# cSLIM-SA_connectors.net
KiCad netlist of a schematic drawn in Altium Designer
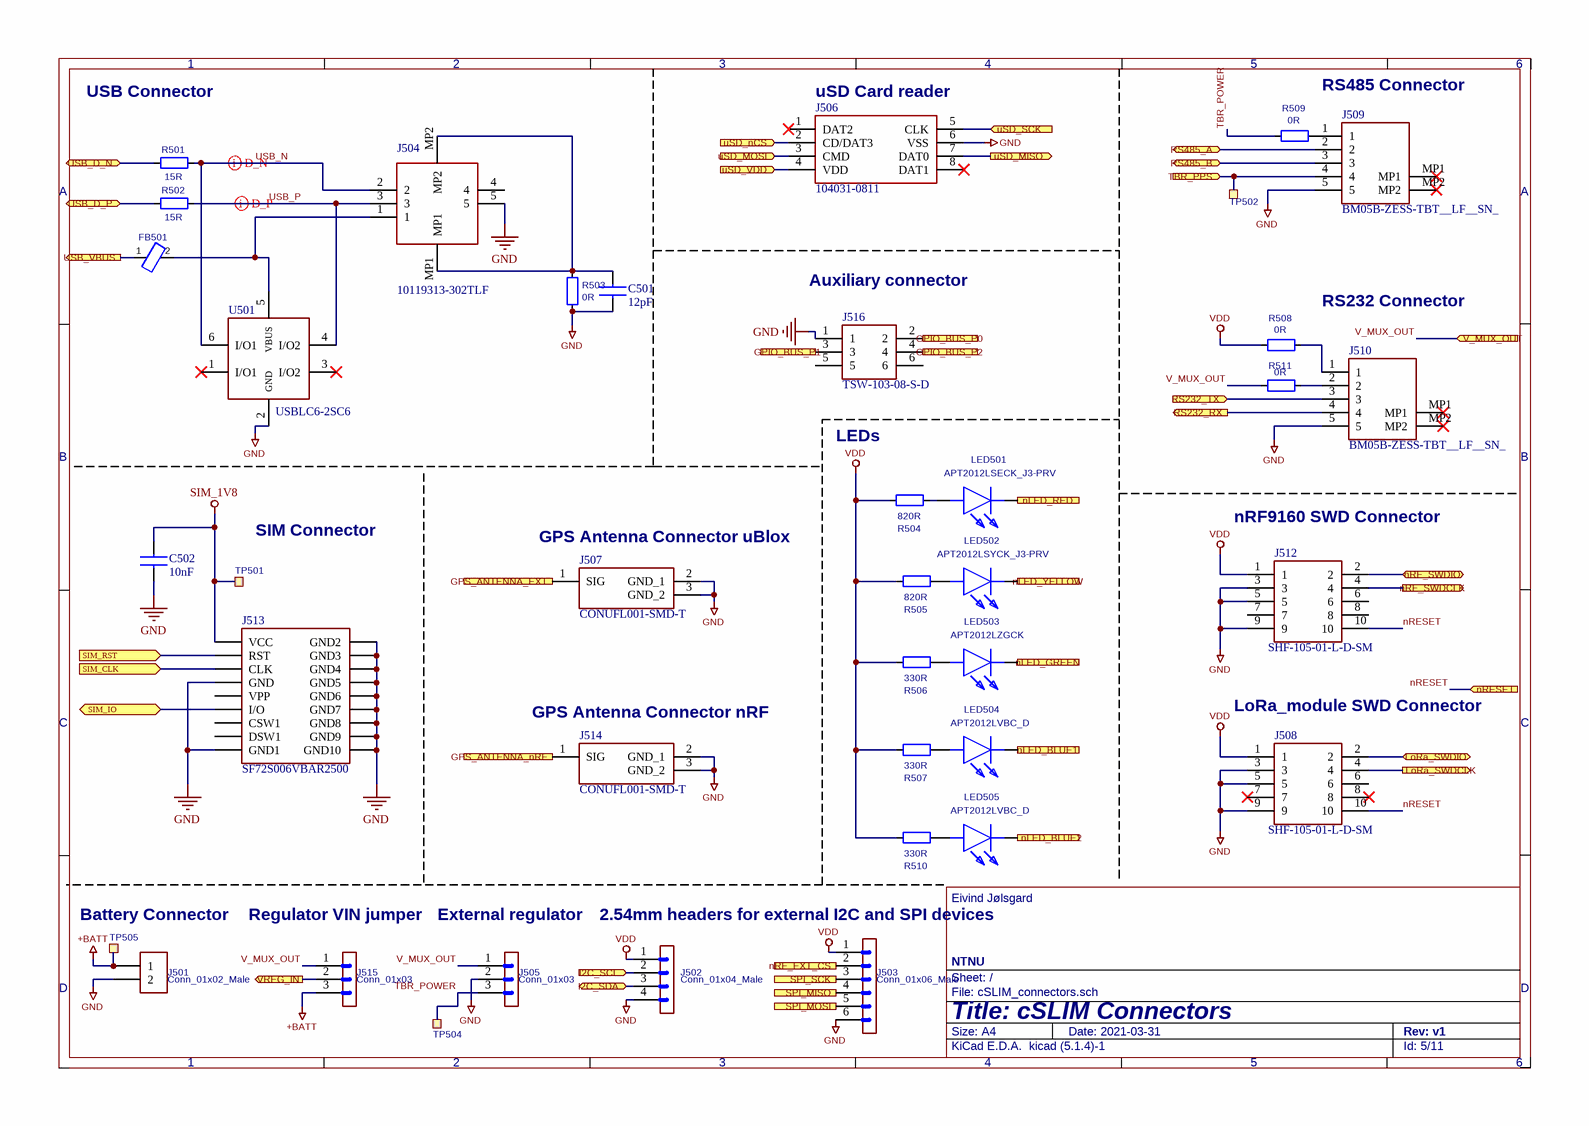
[diagram p0: cSLIM-SA_connectors.SchDoc]

(export (version "E")
  (design (tool "Eeschema 10.0.6"))
  (components
    (comp (ref "C501")
      (value "12pF")
      (footprint "cSLIM-SA:CAPC1608X90N")
      (description "Capacitor")
      (fields
        (field (name "MANUFACTURER_PART_NUMBER") "06033G104ZAT2A")
        (field (name "MOUSER PART NUMBER") "581-06033G104Z")
      )
      (libsource (lib "cSLIM-SA") (part "C"))
    )
    (comp (ref "C502")
      (value "10nF")
      (footprint "cSLIM-SA:CAPC1608X90N")
      (description "Capacitor")
      (fields
        (field (name "MANUFACTURER_PART_NUMBER") "06033G104ZAT2A")
        (field (name "MOUSER PART NUMBER") "581-06033G104Z")
      )
      (libsource (lib "cSLIM-SA") (part "C"))
    )
    (comp (ref "FB501")
      (value "500mA")
      (footprint "CAPC1608X90N")
      (libsource (lib "cSLIM-SA") (part "Ferrite_Bead"))
    )
    (comp (ref "J501")
      (value "Conn_01x02_Male")
      (footprint "cSLIM-SA:SHDR2W64P0X254_1X2_737X660X1181P")
      (description "Connector")
      (fields
        (field (name "MANUFACTURER_PART_NUMBER") "70543-0001")
        (field (name "MOUSER PART NUMBER") "538-70543-0001")
      )
      (libsource (lib "cSLIM-SA") (part "70543-0001"))
    )
    (comp (ref "J502")
      (value "Conn_01x04_Male")
      (footprint "cSLIM-SA:HDRV4W64P0X254_1X4_1016X250X901P")
      (description "Connector")
      (fields (field (name "MANUFACTURER_PART_NUMBER") "PH1-04-UA"))
      (libsource (lib "cSLIM-SA") (part "PH1-04-UA"))
    )
    (comp (ref "J503")
      (value "Conn_01x06_Male")
      (footprint "cSLIM-SA:HDRV6W64P0X254_1X6_1524X254X869P")
      (description "Connector")
      (fields
        (field (name "MANUFACTURER_PART_NUMBER") "61300611121")
        (field (name "MOUSER PART NUMBER") "710-61300611121")
      )
      (libsource (lib "cSLIM-SA") (part "61300611121"))
    )
    (comp (ref "J504")
      (value "10119313-302TLF")
      (footprint "cSLIM-SA:10119313302TLF")
      (description "Connector")
      (fields (field (name "MOUSER PART NUMBER") "649-10119313-302TLF"))
      (libsource (lib "cSLIM-SA") (part "10119313-302TLF"))
    )
    (comp (ref "J505")
      (value "Conn_01x03")
      (footprint "cSLIM-SA:HDRV3W64P0X254_1X3_762X254X869P")
      (description "Connector")
      (fields
        (field (name "MANUFACTURER_PART_NUMBER") "61300311121")
        (field (name "MOUSER PART NUMBER") "710-61300311121")
      )
      (libsource (lib "cSLIM-SA") (part "61300311121"))
    )
    (comp (ref "J506")
      (value "104031-0811")
      (footprint "cSLIM-SA:1040310811")
      (description "Connector")
      (fields (field (name "MOUSER PART NUMBER") "538-104031-0811"))
      (libsource (lib "cSLIM-SA") (part "104031-0811"))
    )
    (comp (ref "J507")
      (value "CONUFL001-SMD-T")
      (footprint "cSLIM-SA:CONUFL001-SMD")
      (description "Connector")
      (fields (field (name "MOUSER PART NUMBER") "712-CONUFL001-SMD-T"))
      (libsource (lib "cSLIM-SA") (part "CONUFL001-SMD-T"))
    )
    (comp (ref "J508")
      (value "SHF-105-01-L-D-SM")
      (footprint "cSLIM-SA:SHF10501LDSMLCKTR")
      (description "Connector")
      (fields (field (name "MANUFACTURER_PART_NUMBER") "SHF-105-01-L-D-SM-LC-K-TR"))
      (libsource (lib "cSLIM-SA") (part "SHF-105-01-L-D-SM-LC-K-TR"))
    )
    (comp (ref "J509")
      (value "BM05B-ZESS-TBT__LF__SN_")
      (footprint "cSLIM-SA:BM05BZESSTBTLFSN")
      (description "Connector")
      (fields (field (name "MANUFACTURER_PART_NUMBER") "BM05B-ZESS-TBT (LF)(SN)"))
      (libsource (lib "cSLIM-SA") (part "BM05B-ZESS-TBT__LF__SN_"))
    )
    (comp (ref "J510")
      (value "BM05B-ZESS-TBT__LF__SN_")
      (footprint "cSLIM-SA:BM05BZESSTBTLFSN")
      (description "Connector")
      (fields (field (name "MANUFACTURER_PART_NUMBER") "BM05B-ZESS-TBT (LF)(SN)"))
      (libsource (lib "cSLIM-SA") (part "BM05B-ZESS-TBT__LF__SN_"))
    )
    (comp (ref "J512")
      (value "SHF-105-01-L-D-SM")
      (footprint "cSLIM-SA:SHF10501LDSMLCKTR")
      (description "Connector")
      (fields (field (name "MANUFACTURER_PART_NUMBER") "SHF-105-01-L-D-SM-LC-K-TR"))
      (libsource (lib "cSLIM-SA") (part "SHF-105-01-L-D-SM-LC-K-TR"))
    )
    (comp (ref "J513")
      (value "SF72S006VBAR2500")
      (footprint "cSLIM-SA:SF72S006VBAR2500")
      (description "Connector")
      (fields (field (name "MOUSER PART NUMBER") "656-SF72S006VBAR2500"))
      (libsource (lib "cSLIM-SA") (part "SF72S006VBAR2500"))
    )
    (comp (ref "J514")
      (value "CONUFL001-SMD-T")
      (footprint "cSLIM-SA:CONUFL001-SMD")
      (description "Connector")
      (fields (field (name "MOUSER PART NUMBER") "712-CONUFL001-SMD-T"))
      (libsource (lib "cSLIM-SA") (part "CONUFL001-SMD-T"))
    )
    (comp (ref "J515")
      (value "Conn_01x03")
      (footprint "cSLIM-SA:HDRV3W64P0X254_1X3_762X254X869P")
      (description "Connector")
      (fields
        (field (name "MANUFACTURER_PART_NUMBER") "61300311121")
        (field (name "MOUSER PART NUMBER") "710-61300311121")
      )
      (libsource (lib "cSLIM-SA") (part "61300311121"))
    )
    (comp (ref "J516")
      (value "TSW-103-08-S-D")
      (footprint "cSLIM-SA:HDRV6W64P254_2X3_762X495X838P")
      (description "Connector")
      (fields (field (name "MOUSER PART NUMBER") "200-TSW10308SD"))
      (libsource (lib "cSLIM-SA") (part "TSW-103-08-S-D"))
    )
    (comp (ref "LED501")
      (value "APT2012LSECK_J3-PRV")
      (footprint "cSLIM-SA:LEDC2012X75N")
      (description "LED")
      (fields
        (field (name "MANUFACTURER_PART_NUMBER") "APT2012LSECK/J3-PRV")
        (field (name "MOUSER PART NUMBER") "604-APT2012LSECKJ3RV")
      )
      (libsource (lib "cSLIM-SA") (part "APT2012LSECK_J3-PRV"))
    )
    (comp (ref "LED502")
      (value "APT2012LSYCK_J3-PRV")
      (footprint "LEDC2012X85N")
      (description "LED")
      (fields
        (field (name "MANUFACTURER_PART_NUMBER") "APT2012LSYCK/J3-PRV")
        (field (name "MOUSER PART NUMBER") "604-APT2012LSYCKJ3RV")
      )
      (libsource (lib "cSLIM-SA") (part "APT2012LSYCK_J3-PRV"))
    )
    (comp (ref "LED503")
      (value "APT2012LZGCK")
      (footprint "cSLIM-SA:LEDC2012X85N")
      (description "LED")
      (fields (field (name "MOUSER PART NUMBER") "604-APT2012LZGCK"))
      (libsource (lib "cSLIM-SA") (part "APT2012LZGCK"))
    )
    (comp (ref "LED504")
      (value "APT2012LVBC_D")
      (footprint "cSLIM-SA:LEDC2012X85N")
      (description "LED")
      (fields
        (field (name "MANUFACTURER_PART_NUMBER") "APT2012LVBC/D")
        (field (name "MOUSER PART NUMBER") "604-APT2012LVBCD")
      )
      (libsource (lib "cSLIM-SA") (part "APT2012LVBC_D"))
    )
    (comp (ref "LED505")
      (value "APT2012LVBC_D")
      (footprint "cSLIM-SA:LEDC2012X85N")
      (description "LED")
      (fields
        (field (name "MANUFACTURER_PART_NUMBER") "APT2012LVBC/D")
        (field (name "MOUSER PART NUMBER") "604-APT2012LVBCD")
      )
      (libsource (lib "cSLIM-SA") (part "APT2012LVBC_D"))
    )
    (comp (ref "R501") (value "15R") (footprint "RESC1608X55N") (libsource (lib "cSLIM-SA") (part "R")))
    (comp (ref "R502") (value "15R") (footprint "RESC1608X55N") (libsource (lib "cSLIM-SA") (part "R")))
    (comp (ref "R503") (value "0R") (footprint "RESC1608X55N") (libsource (lib "") (part "R_1")))
    (comp (ref "R504") (value "820R") (footprint "RESC1608X55N") (libsource (lib "cSLIM-SA") (part "R")))
    (comp (ref "R505") (value "820R") (footprint "RESC1608X55N") (libsource (lib "cSLIM-SA") (part "R")))
    (comp (ref "R506") (value "330R") (footprint "RESC1608X55N") (libsource (lib "cSLIM-SA") (part "R")))
    (comp (ref "R507") (value "330R") (footprint "RESC1608X55N") (libsource (lib "cSLIM-SA") (part "R")))
    (comp (ref "R508") (value "0R") (footprint "RESC1608X55N") (libsource (lib "cSLIM-SA") (part "R")))
    (comp (ref "R509") (value "0R") (footprint "RESC1608X55N") (libsource (lib "cSLIM-SA") (part "R")))
    (comp (ref "R510") (value "330R") (footprint "RESC1608X55N") (libsource (lib "cSLIM-SA") (part "R")))
    (comp (ref "R511") (value "0R") (footprint "RESC1608X55N") (libsource (lib "cSLIM-SA") (part "R")))
    (comp (ref "TP501")
      (value "~")
      (footprint "cSLIM-SA:TP_SMD_Ø1.0mm")
      (libsource (lib "cSLIM-SA") (part "TP"))
    )
    (comp (ref "TP502") (value "~") (footprint "cSLIM-SA:TP_SMD_Ø1.0mm") (libsource (lib "") (part "TP_1")))
    (comp (ref "TP504") (value "~") (footprint "cSLIM-SA:TP_SMD_Ø1.0mm") (libsource (lib "") (part "TP_1")))
    (comp (ref "TP505") (value "~") (footprint "cSLIM-SA:TP_SMD_Ø1.0mm") (libsource (lib "") (part "TP_2")))
    (comp (ref "U501")
      (value "USBLC6-2SC6")
      (footprint "cSLIM-SA:SOT95P280X145-6N")
      (description "Integrated Circuit")
      (fields (field (name "MOUSER PART NUMBER") "511-USBLC6-2SC6"))
      (libsource (lib "cSLIM-SA") (part "USBLC6-2SC6"))
    )
  )
  (nets
    (net (code "1") (name "+BATT") (class "Default")
      (node (ref "J501") (pin "1") (pinfunction "1_1") (pintype "passive"))
      (node (ref "J515") (pin "3") (pinfunction "3_3") (pintype "passive"))
      (node (ref "TP505") (pin "1") (pinfunction "1_1") (pintype "passive"))
    )
    (net (code "2") (name "/GPIO_BUS_P0") (class "Default")
      (node (ref "J516") (pin "2") (pinfunction "2_2") (pintype "passive"))
    )
    (net (code "3") (name "/GPIO_BUS_P1") (class "Default")
      (node (ref "J516") (pin "3") (pinfunction "3_3") (pintype "passive"))
    )
    (net (code "4") (name "/GPIO_BUS_P2") (class "Default")
      (node (ref "J516") (pin "4") (pinfunction "4_4") (pintype "passive"))
    )
    (net (code "5") (name "/GPS_ANTENNA_EXT") (class "Default")
      (node (ref "J507") (pin "1") (pinfunction "SIG_1") (pintype "passive"))
    )
    (net (code "6") (name "/GPS_ANTENNA_nRF") (class "Default")
      (node (ref "J514") (pin "1") (pinfunction "SIG_1") (pintype "passive"))
    )
    (net (code "7") (name "/I2C_SCL") (class "Default")
      (node (ref "J502") (pin "2") (pinfunction "2_2") (pintype "passive"))
    )
    (net (code "8") (name "/I2C_SDA") (class "Default")
      (node (ref "J502") (pin "3") (pinfunction "3_3") (pintype "passive"))
    )
    (net (code "9") (name "/LoRa_SWDCLK") (class "Default")
      (node (ref "J508") (pin "4") (pinfunction "4_4") (pintype "passive"))
    )
    (net (code "10") (name "/LoRa_SWDIO") (class "Default")
      (node (ref "J508") (pin "2") (pinfunction "2_2") (pintype "passive"))
    )
    (net (code "11") (name "/RS232_RX") (class "Default")
      (node (ref "J510") (pin "4") (pinfunction "4_4") (pintype "passive"))
    )
    (net (code "12") (name "/RS232_TX") (class "Default")
      (node (ref "J510") (pin "3") (pinfunction "3_3") (pintype "passive"))
    )
    (net (code "13") (name "/RS485_A") (class "Default")
      (node (ref "J509") (pin "2") (pinfunction "2_2") (pintype "passive"))
    )
    (net (code "14") (name "/RS485_B") (class "Default")
      (node (ref "J509") (pin "3") (pinfunction "3_3") (pintype "passive"))
    )
    (net (code "15") (name "/SIM_CLK") (class "Default")
      (node (ref "J513") (pin "C3") (pinfunction "CLK_C3") (pintype "passive"))
    )
    (net (code "16") (name "/SIM_IO") (class "Default")
      (node (ref "J513") (pin "C7") (pinfunction "I/O_C7") (pintype "passive"))
    )
    (net (code "17") (name "/SIM_RST") (class "Default")
      (node (ref "J513") (pin "C2") (pinfunction "RST_C2") (pintype "passive"))
    )
    (net (code "18") (name "/SPI_MISO") (class "Default")
      (node (ref "J503") (pin "4") (pinfunction "4_4") (pintype "passive"))
    )
    (net (code "19") (name "/SPI_MOSI") (class "Default")
      (node (ref "J503") (pin "5") (pinfunction "5_5") (pintype "passive"))
    )
    (net (code "20") (name "/SPI_SCK") (class "Default")
      (node (ref "J503") (pin "3") (pinfunction "3_3") (pintype "passive"))
    )
    (net (code "21") (name "/TBR_POWER") (class "Default")
      (node (ref "J505") (pin "3") (pinfunction "3_3") (pintype "passive"))
      (node (ref "R509") (pin "2") (pinfunction "2_2") (pintype "passive"))
      (node (ref "TP504") (pin "1") (pinfunction "1_1") (pintype "passive"))
    )
    (net (code "22") (name "/TBR_PPS") (class "Default")
      (node (ref "J509") (pin "4") (pinfunction "4_4") (pintype "passive"))
      (node (ref "TP502") (pin "1") (pinfunction "1_1") (pintype "passive"))
    )
    (net (code "23") (name "/USB_D_N") (class "Default")
      (node (ref "R501") (pin "2") (pinfunction "2_2") (pintype "passive"))
    )
    (net (code "24") (name "/USB_D_P") (class "Default")
      (node (ref "R502") (pin "2") (pinfunction "2_2") (pintype "passive"))
    )
    (net (code "25") (name "/USB_N") (class "Default")
      (node (ref "J504") (pin "2") (pinfunction "2_2") (pintype "passive"))
      (node (ref "R501") (pin "1") (pinfunction "1_1") (pintype "passive"))
      (node (ref "U501") (pin "6") (pinfunction "I/O1_6") (pintype "passive"))
    )
    (net (code "26") (name "/USB_P") (class "Default")
      (node (ref "J504") (pin "3") (pinfunction "3_3") (pintype "passive"))
      (node (ref "R502") (pin "1") (pinfunction "1_1") (pintype "passive"))
      (node (ref "U501") (pin "4") (pinfunction "I/O2_4") (pintype "passive"))
    )
    (net (code "27") (name "/USB_VBUS") (class "Default")
      (node (ref "FB501") (pin "1") (pinfunction "1_1") (pintype "passive"))
    )
    (net (code "28") (name "/VREG_IN") (class "Default")
      (node (ref "J515") (pin "2") (pinfunction "2_2") (pintype "passive"))
    )
    (net (code "29") (name "/V_MUX_OUT") (class "Default")
      (node (ref "J505") (pin "1") (pinfunction "1_1") (pintype "passive"))
      (node (ref "J515") (pin "1") (pinfunction "1_1") (pintype "passive"))
      (node (ref "R511") (pin "2") (pinfunction "2_2") (pintype "passive"))
    )
    (net (code "30") (name "/nLED_BLUE1") (class "Default")
      (node (ref "LED504") (pin "1") (pinfunction "K_1") (pintype "passive"))
    )
    (net (code "31") (name "/nLED_BLUE2") (class "Default")
      (node (ref "LED505") (pin "1") (pinfunction "K_1") (pintype "passive"))
    )
    (net (code "32") (name "/nLED_GREEN") (class "Default")
      (node (ref "LED503") (pin "1") (pinfunction "K_1") (pintype "passive"))
    )
    (net (code "33") (name "/nLED_RED") (class "Default")
      (node (ref "LED501") (pin "1") (pinfunction "K_1") (pintype "passive"))
    )
    (net (code "34") (name "/nLED_YELLOW") (class "Default")
      (node (ref "LED502") (pin "1") (pinfunction "K_1") (pintype "passive"))
    )
    (net (code "35") (name "/nRESET") (class "Default")
      (node (ref "J508") (pin "10") (pinfunction "10_10") (pintype "passive"))
      (node (ref "J512") (pin "10") (pinfunction "10_10") (pintype "passive"))
    )
    (net (code "36") (name "/nRF_EXT_CS") (class "Default")
      (node (ref "J503") (pin "2") (pinfunction "2_2") (pintype "passive"))
    )
    (net (code "37") (name "/nRF_SWDCLK") (class "Default")
      (node (ref "J512") (pin "4") (pinfunction "4_4") (pintype "passive"))
    )
    (net (code "38") (name "/nRF_SWDIO") (class "Default")
      (node (ref "J512") (pin "2") (pinfunction "2_2") (pintype "passive"))
    )
    (net (code "39") (name "/uSD_MISO") (class "Default")
      (node (ref "J506") (pin "7") (pinfunction "DAT0_7") (pintype "passive"))
    )
    (net (code "40") (name "/uSD_MOSI") (class "Default")
      (node (ref "J506") (pin "3") (pinfunction "CMD_3") (pintype "passive"))
    )
    (net (code "41") (name "/uSD_SCK") (class "Default")
      (node (ref "J506") (pin "5") (pinfunction "CLK_5") (pintype "passive"))
    )
    (net (code "42") (name "/uSD_VDD") (class "Default")
      (node (ref "J506") (pin "4") (pinfunction "VDD_4") (pintype "passive"))
    )
    (net (code "43") (name "/uSD_nCS") (class "Default")
      (node (ref "J506") (pin "2") (pinfunction "CD/DAT3_2") (pintype "passive"))
    )
    (net (code "44") (name "GND") (class "Default")
      (node (ref "C501") (pin "2") (pinfunction "2_2") (pintype "passive"))
      (node (ref "C502") (pin "2") (pinfunction "2_2") (pintype "passive"))
      (node (ref "J501") (pin "2") (pinfunction "2_2") (pintype "passive"))
      (node (ref "J502") (pin "4") (pinfunction "4_4") (pintype "passive"))
      (node (ref "J503") (pin "6") (pinfunction "6_6") (pintype "passive"))
      (node (ref "J504") (pin "5") (pinfunction "5_5") (pintype "passive"))
      (node (ref "J505") (pin "2") (pinfunction "2_2") (pintype "passive"))
      (node (ref "J506") (pin "6") (pinfunction "VSS_6") (pintype "passive"))
      (node (ref "J507") (pin "2") (pinfunction "GND_1_2") (pintype "passive"))
      (node (ref "J507") (pin "3") (pinfunction "GND_2_3") (pintype "passive"))
      (node (ref "J508") (pin "3") (pinfunction "3_3") (pintype "passive"))
      (node (ref "J508") (pin "5") (pinfunction "5_5") (pintype "passive"))
      (node (ref "J508") (pin "9") (pinfunction "9_9") (pintype "passive"))
      (node (ref "J509") (pin "5") (pinfunction "5_5") (pintype "passive"))
      (node (ref "J510") (pin "5") (pinfunction "5_5") (pintype "passive"))
      (node (ref "J512") (pin "3") (pinfunction "3_3") (pintype "passive"))
      (node (ref "J512") (pin "5") (pinfunction "5_5") (pintype "passive"))
      (node (ref "J512") (pin "9") (pinfunction "9_9") (pintype "passive"))
      (node (ref "J513") (pin "C5") (pinfunction "GND_C5") (pintype "passive"))
      (node (ref "J513") (pin "GND1") (pinfunction "GND1_GND1") (pintype "passive"))
      (node (ref "J513") (pin "GND10") (pinfunction "GND10_GND10") (pintype "passive"))
      (node (ref "J513") (pin "GND2") (pinfunction "GND2_GND2") (pintype "passive"))
      (node (ref "J513") (pin "GND3") (pinfunction "GND3_GND3") (pintype "passive"))
      (node (ref "J513") (pin "GND4") (pinfunction "GND4_GND4") (pintype "passive"))
      (node (ref "J513") (pin "GND5") (pinfunction "GND5_GND5") (pintype "passive"))
      (node (ref "J513") (pin "GND6") (pinfunction "GND6_GND6") (pintype "passive"))
      (node (ref "J513") (pin "GND7") (pinfunction "GND7_GND7") (pintype "passive"))
      (node (ref "J513") (pin "GND8") (pinfunction "GND8_GND8") (pintype "passive"))
      (node (ref "J513") (pin "GND9") (pinfunction "GND9_GND9") (pintype "passive"))
      (node (ref "J514") (pin "2") (pinfunction "GND_1_2") (pintype "passive"))
      (node (ref "J514") (pin "3") (pinfunction "GND_2_3") (pintype "passive"))
      (node (ref "J516") (pin "1") (pinfunction "1_1") (pintype "passive"))
      (node (ref "R503") (pin "2") (pinfunction "2_2") (pintype "passive"))
      (node (ref "U501") (pin "2") (pinfunction "GND_2") (pintype "passive"))
    )
    (net (code "45") (name "Net-(C501-Pad1)") (class "Default")
      (node (ref "C501") (pin "1") (pinfunction "1_1") (pintype "passive"))
      (node (ref "J504") (pin "MP1") (pinfunction "MP1_MP1") (pintype "passive"))
      (node (ref "J504") (pin "MP2") (pinfunction "MP2_MP2") (pintype "passive"))
      (node (ref "R503") (pin "1") (pinfunction "1_1") (pintype "passive"))
    )
    (net (code "46") (name "Net-(J509-Pad1)") (class "Default")
      (node (ref "J509") (pin "1") (pinfunction "1_1") (pintype "passive"))
      (node (ref "R509") (pin "1") (pinfunction "1_1") (pintype "passive"))
    )
    (net (code "47") (name "Net-(J510-Pad1)") (class "Default")
      (node (ref "J510") (pin "1") (pinfunction "1_1") (pintype "passive"))
      (node (ref "R508") (pin "1") (pinfunction "1_1") (pintype "passive"))
    )
    (net (code "48") (name "Net-(J510-Pad2)") (class "Default")
      (node (ref "J510") (pin "2") (pinfunction "2_2") (pintype "passive"))
      (node (ref "R511") (pin "1") (pinfunction "1_1") (pintype "passive"))
    )
    (net (code "49") (name "Net-(LED501-A)") (class "Default")
      (node (ref "LED501") (pin "2") (pinfunction "A_2") (pintype "passive"))
      (node (ref "R504") (pin "1") (pinfunction "1_1") (pintype "passive"))
    )
    (net (code "50") (name "Net-(LED502-A)") (class "Default")
      (node (ref "LED502") (pin "2") (pinfunction "A_2") (pintype "passive"))
      (node (ref "R505") (pin "1") (pinfunction "1_1") (pintype "passive"))
    )
    (net (code "51") (name "Net-(LED503-A)") (class "Default")
      (node (ref "LED503") (pin "2") (pinfunction "A_2") (pintype "passive"))
      (node (ref "R506") (pin "1") (pinfunction "1_1") (pintype "passive"))
    )
    (net (code "52") (name "Net-(LED504-A)") (class "Default")
      (node (ref "LED504") (pin "2") (pinfunction "A_2") (pintype "passive"))
      (node (ref "R507") (pin "1") (pinfunction "1_1") (pintype "passive"))
    )
    (net (code "53") (name "Net-(LED505-A)") (class "Default")
      (node (ref "LED505") (pin "2") (pinfunction "A_2") (pintype "passive"))
      (node (ref "R510") (pin "1") (pinfunction "1_1") (pintype "passive"))
    )
    (net (code "54") (name "Net-(U501-VBUS)") (class "Default")
      (node (ref "FB501") (pin "2") (pinfunction "2_2") (pintype "passive"))
      (node (ref "J504") (pin "1") (pinfunction "1_1") (pintype "passive"))
      (node (ref "U501") (pin "5") (pinfunction "VBUS_5") (pintype "passive"))
    )
    (net (code "55") (name "SIM_1V8") (class "Default")
      (node (ref "C502") (pin "1") (pinfunction "1_1") (pintype "passive"))
      (node (ref "J513") (pin "C1") (pinfunction "VCC_C1") (pintype "passive"))
      (node (ref "TP501") (pin "1") (pinfunction "1_1") (pintype "passive"))
    )
    (net (code "56") (name "VDD") (class "Default")
      (node (ref "J502") (pin "1") (pinfunction "1_1") (pintype "passive"))
      (node (ref "J503") (pin "1") (pinfunction "1_1") (pintype "passive"))
      (node (ref "J508") (pin "1") (pinfunction "1_1") (pintype "passive"))
      (node (ref "J512") (pin "1") (pinfunction "1_1") (pintype "passive"))
      (node (ref "R504") (pin "2") (pinfunction "2_2") (pintype "passive"))
      (node (ref "R505") (pin "2") (pinfunction "2_2") (pintype "passive"))
      (node (ref "R506") (pin "2") (pinfunction "2_2") (pintype "passive"))
      (node (ref "R507") (pin "2") (pinfunction "2_2") (pintype "passive"))
      (node (ref "R508") (pin "2") (pinfunction "2_2") (pintype "passive"))
      (node (ref "R510") (pin "2") (pinfunction "2_2") (pintype "passive"))
    )
    (net (code "57") (name "unconnected-(J504-Pad4)") (class "Default")
      (node (ref "J504") (pin "4") (pinfunction "4_4") (pintype "passive"))
    )
    (net (code "58") (name "unconnected-(J506-DAT1-Pad8)") (class "Default")
      (node (ref "J506") (pin "8") (pinfunction "DAT1_8") (pintype "passive+no_connect"))
    )
    (net (code "59") (name "unconnected-(J506-DAT2-Pad1)") (class "Default")
      (node (ref "J506") (pin "1") (pinfunction "DAT2_1") (pintype "passive+no_connect"))
    )
    (net (code "60") (name "unconnected-(J508-Pad6)") (class "Default")
      (node (ref "J508") (pin "6") (pinfunction "6_6") (pintype "passive"))
    )
    (net (code "61") (name "unconnected-(J508-Pad7)") (class "Default")
      (node (ref "J508") (pin "7") (pinfunction "7_7") (pintype "passive+no_connect"))
    )
    (net (code "62") (name "unconnected-(J508-Pad8)") (class "Default")
      (node (ref "J508") (pin "8") (pinfunction "8_8") (pintype "passive+no_connect"))
    )
    (net (code "63") (name "unconnected-(J509-PadMP1)") (class "Default")
      (node (ref "J509") (pin "MP1") (pinfunction "MP1_MP1") (pintype "passive+no_connect"))
    )
    (net (code "64") (name "unconnected-(J509-PadMP2)") (class "Default")
      (node (ref "J509") (pin "MP2") (pinfunction "MP2_MP2") (pintype "passive+no_connect"))
    )
    (net (code "65") (name "unconnected-(J510-PadMP1)") (class "Default")
      (node (ref "J510") (pin "MP1") (pinfunction "MP1_MP1") (pintype "passive+no_connect"))
    )
    (net (code "66") (name "unconnected-(J510-PadMP2)") (class "Default")
      (node (ref "J510") (pin "MP2") (pinfunction "MP2_MP2") (pintype "passive+no_connect"))
    )
    (net (code "67") (name "unconnected-(J512-Pad6)") (class "Default")
      (node (ref "J512") (pin "6") (pinfunction "6_6") (pintype "passive"))
    )
    (net (code "68") (name "unconnected-(J512-Pad7)") (class "Default")
      (node (ref "J512") (pin "7") (pinfunction "7_7") (pintype "passive"))
    )
    (net (code "69") (name "unconnected-(J512-Pad8)") (class "Default")
      (node (ref "J512") (pin "8") (pinfunction "8_8") (pintype "passive"))
    )
    (net (code "70") (name "unconnected-(J513-PadCSW1)") (class "Default")
      (node (ref "J513") (pin "CSW1") (pinfunction "CSW1_CSW1") (pintype "passive"))
    )
    (net (code "71") (name "unconnected-(J513-PadDSW1)") (class "Default")
      (node (ref "J513") (pin "DSW1") (pinfunction "DSW1_DSW1") (pintype "passive"))
    )
    (net (code "72") (name "unconnected-(J513-VPP-PadC6)") (class "Default")
      (node (ref "J513") (pin "C6") (pinfunction "VPP_C6") (pintype "passive"))
    )
    (net (code "73") (name "unconnected-(J516-Pad5)") (class "Default")
      (node (ref "J516") (pin "5") (pinfunction "5_5") (pintype "passive"))
    )
    (net (code "74") (name "unconnected-(J516-Pad6)") (class "Default")
      (node (ref "J516") (pin "6") (pinfunction "6_6") (pintype "passive"))
    )
    (net (code "75") (name "unconnected-(U501-I{slash}O1-Pad1)") (class "Default")
      (node (ref "U501") (pin "1") (pinfunction "I/O1_1") (pintype "passive+no_connect"))
    )
    (net (code "76") (name "unconnected-(U501-I{slash}O2-Pad3)") (class "Default")
      (node (ref "U501") (pin "3") (pinfunction "I/O2_3") (pintype "passive+no_connect"))
    )
  )
)
